# rpi-to-pluto.net
KiCad netlist of a schematic drawn in EAGLE
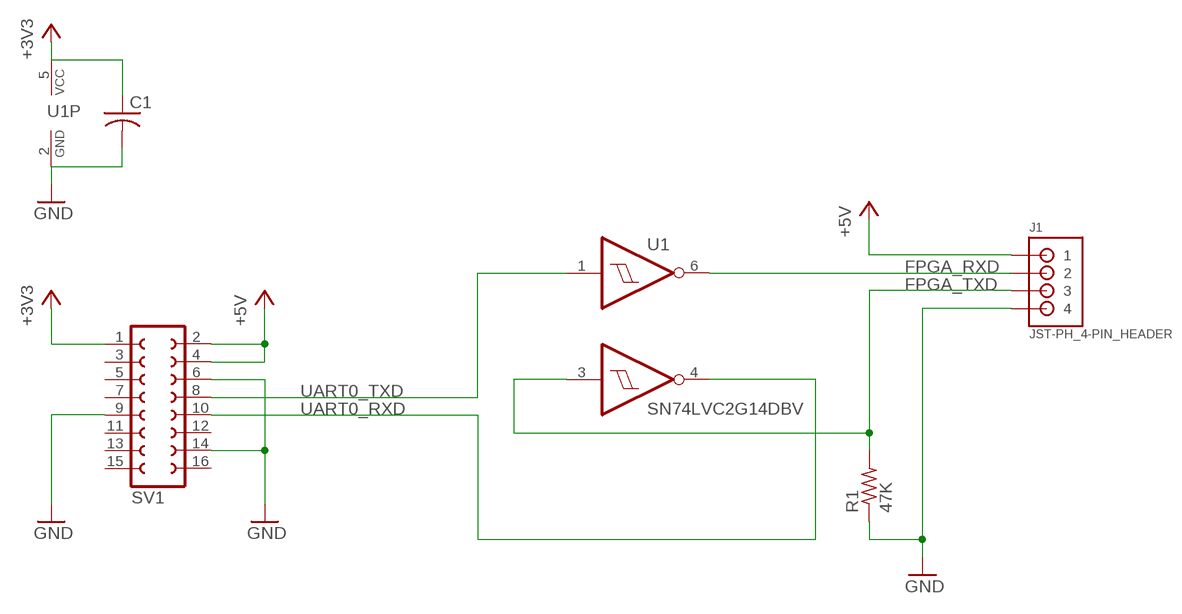
[diagram p0: schematic, sheet 1]

(export (version "E")
  (design (tool "Eeschema 10.0.6"))
  (components
    (comp (ref "C1")
      (value "C-USC0805")
      (footprint "eagle-import:C0805")
      (libsource (lib "eagle-import") (part "C-USC0805"))
    )
    (comp (ref "J1")
      (value "JST-PH_4-PIN_HEADER")
      (footprint "eagle-import:JST_B4B-PH_HEADER")
      (libsource (lib "eagle-import") (part "JST-PH_4-PIN_HEADER"))
    )
    (comp (ref "R1")
      (value "47K")
      (footprint "eagle-import:R0805")
      (libsource (lib "eagle-import") (part "R-US_R0805"))
    )
    (comp (ref "SV1")
      (value "FE08-2")
      (footprint "eagle-import:FE08-2")
      (libsource (lib "eagle-import") (part "FE08-2"))
    )
    (comp (ref "U1")
      (value "SN74LVC2G14DBV")
      (footprint "eagle-import:SOT23-6")
      (libsource (lib "eagle-import") (part "SN742G14DBVLVC"))
    )
  )
  (nets
    (net (code "1") (name "+3V3") (class "Default")
      (node (ref "C1") (pin "1") (pinfunction "1_1") (pintype "passive"))
      (node (ref "SV1") (pin "1") (pinfunction "1_1") (pintype "passive"))
      (node (ref "U1") (pin "5") (pinfunction "VCC_5") (pintype "power_in"))
    )
    (net (code "2") (name "+5V") (class "Default")
      (node (ref "J1") (pin "P1") (pinfunction "1_P1") (pintype "bidirectional"))
      (node (ref "SV1") (pin "2") (pinfunction "2_2") (pintype "passive"))
      (node (ref "SV1") (pin "4") (pinfunction "4_4") (pintype "passive"))
    )
    (net (code "3") (name "/FPGA_RXD") (class "Default")
      (node (ref "J1") (pin "P2") (pinfunction "2_P2") (pintype "bidirectional"))
      (node (ref "U1") (pin "6") (pinfunction "1Y_6") (pintype "output"))
    )
    (net (code "4") (name "/FPGA_TXD") (class "Default")
      (node (ref "J1") (pin "P3") (pinfunction "3_P3") (pintype "bidirectional"))
      (node (ref "R1") (pin "2") (pinfunction "2_2") (pintype "passive"))
      (node (ref "U1") (pin "3") (pinfunction "2A_3") (pintype "input"))
    )
    (net (code "5") (name "/UART0_RXD") (class "Default")
      (node (ref "SV1") (pin "10") (pinfunction "10_10") (pintype "passive"))
      (node (ref "U1") (pin "4") (pinfunction "2Y_4") (pintype "output"))
    )
    (net (code "6") (name "/UART0_TXD") (class "Default")
      (node (ref "SV1") (pin "8") (pinfunction "8_8") (pintype "passive"))
      (node (ref "U1") (pin "1") (pinfunction "1A_1") (pintype "input"))
    )
    (net (code "7") (name "GND") (class "Default")
      (node (ref "C1") (pin "2") (pinfunction "2_2") (pintype "passive"))
      (node (ref "J1") (pin "P4") (pinfunction "4_P4") (pintype "bidirectional"))
      (node (ref "R1") (pin "1") (pinfunction "1_1") (pintype "passive"))
      (node (ref "SV1") (pin "14") (pinfunction "14_14") (pintype "passive"))
      (node (ref "SV1") (pin "6") (pinfunction "6_6") (pintype "passive"))
      (node (ref "SV1") (pin "9") (pinfunction "9_9") (pintype "passive"))
      (node (ref "U1") (pin "2") (pinfunction "GND_2") (pintype "power_in"))
    )
    (net (code "8") (name "unconnected-(SV1-Pad3)") (class "Default")
      (node (ref "SV1") (pin "3") (pinfunction "3_3") (pintype "passive"))
    )
    (net (code "9") (name "unconnected-(SV1-Pad5)") (class "Default")
      (node (ref "SV1") (pin "5") (pinfunction "5_5") (pintype "passive"))
    )
    (net (code "10") (name "unconnected-(SV1-Pad7)") (class "Default")
      (node (ref "SV1") (pin "7") (pinfunction "7_7") (pintype "passive"))
    )
    (net (code "11") (name "unconnected-(SV1-Pad11)") (class "Default")
      (node (ref "SV1") (pin "11") (pinfunction "11_11") (pintype "passive"))
    )
    (net (code "12") (name "unconnected-(SV1-Pad12)") (class "Default")
      (node (ref "SV1") (pin "12") (pinfunction "12_12") (pintype "passive"))
    )
    (net (code "13") (name "unconnected-(SV1-Pad13)") (class "Default")
      (node (ref "SV1") (pin "13") (pinfunction "13_13") (pintype "passive"))
    )
    (net (code "14") (name "unconnected-(SV1-Pad15)") (class "Default")
      (node (ref "SV1") (pin "15") (pinfunction "15_15") (pintype "passive"))
    )
    (net (code "15") (name "unconnected-(SV1-Pad16)") (class "Default")
      (node (ref "SV1") (pin "16") (pinfunction "16_16") (pintype "passive"))
    )
  )
)
